# ZUM_Core_Power.net
KiCad netlist of a schematic drawn in Altium Designer
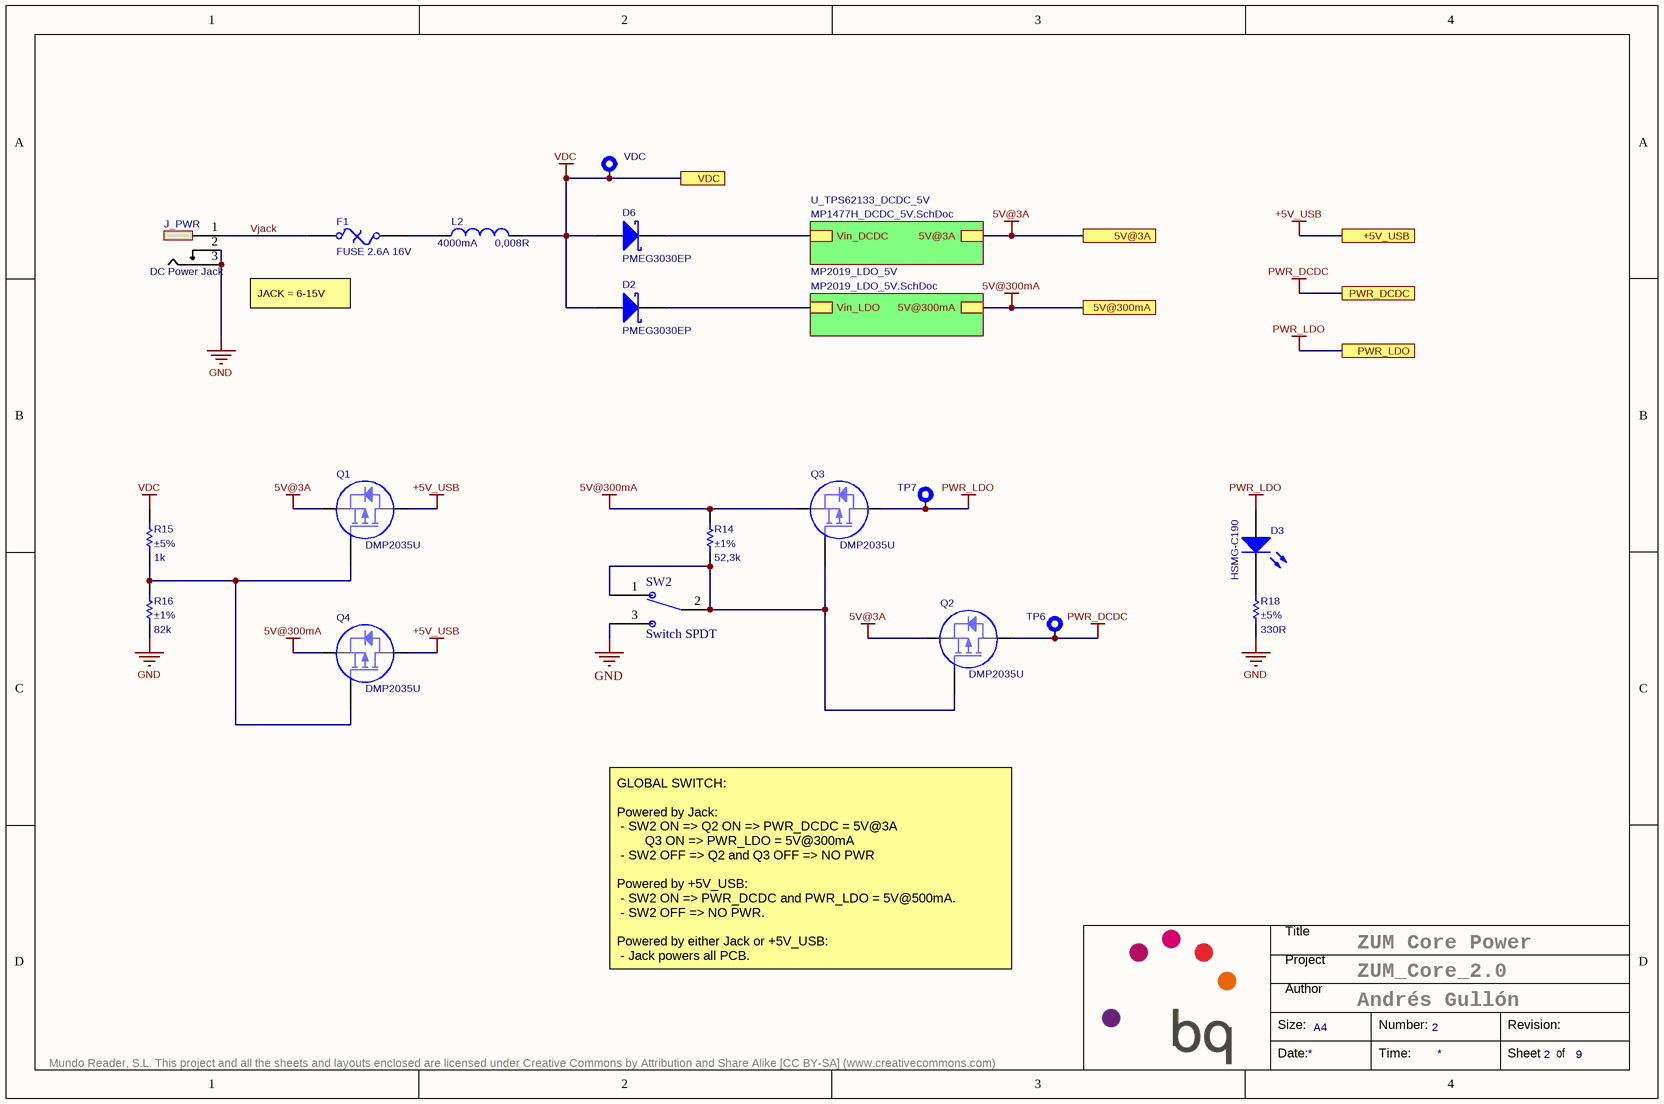
[diagram p0: ZUM_Core_Power.SchDoc]

(export (version "E")
  (design (tool "Eeschema 10.0.6"))
  (components
    (comp (ref "D2")
      (value "PMEG3030EP")
      (footprint "SOD128")
      (description "Schottky Diode")
      (fields (field (name "MANUFACTURER") "NXP"))
      (libsource (lib "BQ Vault") (part "Schottky"))
    )
    (comp (ref "D3")
      (value "HSMG-C190")
      (footprint "LED0603")
      (description "LED")
      (fields (field (name "MANUFACTURER") "Avago Technologies"))
      (libsource (lib "BQ Vault") (part "LED"))
    )
    (comp (ref "D6")
      (value "PMEG3030EP")
      (footprint "SOD128")
      (description "Schottky Diode")
      (fields (field (name "MANUFACTURER") "NXP"))
      (libsource (lib "BQ Vault") (part "Schottky"))
    )
    (comp (ref "F1")
      (value "FUSE 2.6A 16V")
      (footprint "F1812")
      (description "Resettable Fuses")
      (fields (field (name "PART NUMBER") "FUSE 2.5A 16V") (field (name "VOLTAGE") "16V"))
      (libsource (lib "BQ Vault") (part "CMP-A2427-2"))
    )
    (comp (ref "J_PWR")
      (value "DC Power Jack")
      (footprint "Jack 2.1")
      (description "Connector")
      (fields (field (name "MANUFACTURER") "Kycon"))
      (libsource (lib "BQ Vault") (part "Power_Jack"))
    )
    (comp (ref "L2")
      (value "L0805_33R_0,008R_4000mA")
      (footprint "L0805")
      (fields
        (field (name "RESISTANCE_DC") "0,008R")
        (field (name "CURRENT") "4000mA")
        (field (name "MANUFACTURER") "Würth Elektronik")
      )
      (libsource (lib "BQ Vault") (part "CMP-A0714-1"))
    )
    (comp (ref "Q1")
      (value "DMP2035U")
      (footprint "SOT23-3")
      (description "P-MOSFET transistor")
      (fields (field (name "MANUFACTURER") "Diodes Incorporated"))
      (libsource (lib "BQ Vault") (part "CMP-A2378-1"))
    )
    (comp (ref "Q2")
      (value "DMP2035U")
      (footprint "SOT23-3")
      (description "P-MOSFET transistor")
      (fields (field (name "MANUFACTURER") "Diodes Incorporated"))
      (libsource (lib "BQ Vault") (part "CMP-A2378-1"))
    )
    (comp (ref "Q3")
      (value "DMP2035U")
      (footprint "SOT23-3")
      (description "P-MOSFET transistor")
      (fields (field (name "MANUFACTURER") "Diodes Incorporated"))
      (libsource (lib "BQ Vault") (part "CMP-A2378-1"))
    )
    (comp (ref "Q4")
      (value "DMP2035U")
      (footprint "SOT23-3")
      (description "P-MOSFET transistor")
      (fields (field (name "MANUFACTURER") "Diodes Incorporated"))
      (libsource (lib "BQ Vault") (part "CMP-A2378-1"))
    )
    (comp (ref "R14")
      (value "R0402_52,3k_0.063W_±1%")
      (footprint "R0402")
      (fields
        (field (name "TOLERANCE") "±1%")
        (field (name "POWER") "0.063W")
        (field (name "RESISTANCE") "52,3k")
        (field (name "MANUFACTURER") "Vishay")
      )
      (libsource (lib "BQ Vault") (part "Resistor"))
    )
    (comp (ref "R15")
      (value "R0402_1k_0.063W_±5%")
      (footprint "R0402")
      (fields
        (field (name "TOLERANCE") "±5%")
        (field (name "POWER") "0.063W")
        (field (name "RESISTANCE") "1k")
        (field (name "MANUFACTURER") "Vishay")
      )
      (libsource (lib "BQ Vault") (part "Resistor"))
    )
    (comp (ref "R16")
      (value "R0402_82k_0.063W_±1%")
      (footprint "R0402")
      (fields
        (field (name "TOLERANCE") "±1%")
        (field (name "POWER") "0.063W")
        (field (name "RESISTANCE") "82k")
        (field (name "MANUFACTURER") "Vishay")
      )
      (libsource (lib "BQ Vault") (part "Resistor"))
    )
    (comp (ref "R18")
      (value "R0402_330R_0.063W_±5%")
      (footprint "R0402")
      (fields
        (field (name "TOLERANCE") "±5%")
        (field (name "POWER") "0.063W")
        (field (name "RESISTANCE") "330R")
        (field (name "MANUFACTURER") "Vishay")
      )
      (libsource (lib "BQ Vault") (part "CMP-A1762-2"))
    )
    (comp (ref "SW2")
      (value "Switch SPDT")
      (footprint "Slide SW SPDT Right Angle")
      (description "Switch")
      (fields (field (name "MANUFACTURER") "Würth Elektronik"))
      (libsource (lib "BQ Vault") (part "CMP-A2473-1"))
    )
    (comp (ref "TP6")
      (value "TP")
      (footprint "TP_POWER")
      (description "Testpoint 0.3mm")
      (fields (field (name "MANUFACTURER") "Oxley") (field (name "PART NUMBER") "TP_POWER"))
      (libsource (lib "BQ Vault") (part "CMP-A2499-3"))
    )
    (comp (ref "TP7")
      (value "TP")
      (footprint "TP_POWER")
      (description "Testpoint 0.3mm")
      (fields (field (name "MANUFACTURER") "Oxley") (field (name "PART NUMBER") "TP_POWER"))
      (libsource (lib "BQ Vault") (part "CMP-A2499-3"))
    )
    (comp (ref "VDC")
      (value "TP_POWER")
      (footprint "TP_POWER")
      (description "Testpoint 0.3mm")
      (fields (field (name "MANUFACTURER") "Oxley"))
      (libsource (lib "BQ Vault") (part "CMP-A2499-3"))
    )
  )
  (nets
    (net (code "1") (name "+5V_USB") (class "Default")
      (node (ref "Q1") (pin "3") (pinfunction "D_3") (pintype "passive"))
      (node (ref "Q4") (pin "3") (pinfunction "D_3") (pintype "passive"))
    )
    (net (code "2") (name "/Vin_DCDC") (class "Default")
      (node (ref "D6") (pin "k") (pinfunction "K_k") (pintype "passive"))
    )
    (net (code "3") (name "/Vin_LDO") (class "Default")
      (node (ref "D2") (pin "k") (pinfunction "K_k") (pintype "passive"))
    )
    (net (code "4") (name "/Vjack") (class "Default")
      (node (ref "F1") (pin "1") (pinfunction "1_1") (pintype "passive"))
      (node (ref "J_PWR") (pin "1") (pinfunction "1_1") (pintype "passive"))
    )
    (net (code "5") (name "5V@3A") (class "Default")
      (node (ref "Q1") (pin "2") (pinfunction "S_2") (pintype "passive"))
      (node (ref "Q2") (pin "2") (pinfunction "S_2") (pintype "passive"))
    )
    (net (code "6") (name "5V@300mA") (class "Default")
      (node (ref "Q3") (pin "2") (pinfunction "S_2") (pintype "passive"))
      (node (ref "Q4") (pin "2") (pinfunction "S_2") (pintype "passive"))
      (node (ref "R14") (pin "1") (pinfunction "1_1") (pintype "passive"))
    )
    (net (code "7") (name "GND") (class "Default")
      (node (ref "J_PWR") (pin "2") (pinfunction "2_2") (pintype "passive"))
      (node (ref "J_PWR") (pin "3") (pinfunction "3_3") (pintype "passive"))
      (node (ref "R16") (pin "1") (pinfunction "1_1") (pintype "passive"))
      (node (ref "R18") (pin "1") (pinfunction "1_1") (pintype "passive"))
      (node (ref "SW2") (pin "3") (pinfunction "3_3") (pintype "passive"))
    )
    (net (code "8") (name "Net-(D3-PadK)") (class "Default")
      (node (ref "D3") (pin "K") (pinfunction "K_K") (pintype "passive"))
      (node (ref "R18") (pin "2") (pinfunction "2_2") (pintype "passive"))
    )
    (net (code "9") (name "Net-(F1-Pad2)") (class "Default")
      (node (ref "F1") (pin "2") (pinfunction "2_2") (pintype "passive"))
      (node (ref "L2") (pin "1") (pinfunction "1_1") (pintype "passive"))
    )
    (net (code "10") (name "Net-(Q1-G)") (class "Default")
      (node (ref "Q1") (pin "1") (pinfunction "G_1") (pintype "passive"))
      (node (ref "Q4") (pin "1") (pinfunction "G_1") (pintype "passive"))
      (node (ref "R15") (pin "1") (pinfunction "1_1") (pintype "passive"))
      (node (ref "R16") (pin "2") (pinfunction "2_2") (pintype "passive"))
    )
    (net (code "11") (name "Net-(Q2-G)") (class "Default")
      (node (ref "Q2") (pin "1") (pinfunction "G_1") (pintype "passive"))
      (node (ref "Q3") (pin "1") (pinfunction "G_1") (pintype "passive"))
      (node (ref "R14") (pin "2") (pinfunction "2_2") (pintype "passive"))
      (node (ref "SW2") (pin "1") (pinfunction "1_1") (pintype "passive"))
      (node (ref "SW2") (pin "2") (pinfunction "2_2") (pintype "passive"))
    )
    (net (code "12") (name "PWR_DCDC") (class "Default")
      (node (ref "Q2") (pin "3") (pinfunction "D_3") (pintype "passive"))
      (node (ref "TP6") (pin "1") (pinfunction "1_1") (pintype "passive"))
    )
    (net (code "13") (name "PWR_LDO") (class "Default")
      (node (ref "D3") (pin "A") (pinfunction "A_A") (pintype "passive"))
      (node (ref "Q3") (pin "3") (pinfunction "D_3") (pintype "passive"))
      (node (ref "TP7") (pin "1") (pinfunction "1_1") (pintype "passive"))
    )
    (net (code "14") (name "VDC") (class "Default")
      (node (ref "D2") (pin "A") (pinfunction "A_A") (pintype "passive"))
      (node (ref "D6") (pin "A") (pinfunction "A_A") (pintype "passive"))
      (node (ref "L2") (pin "2") (pinfunction "2_2") (pintype "passive"))
      (node (ref "R15") (pin "2") (pinfunction "2_2") (pintype "passive"))
      (node (ref "VDC") (pin "1") (pinfunction "1_1") (pintype "passive"))
    )
  )
)
